# MCU.net
KiCad netlist of a schematic drawn in Altium Designer
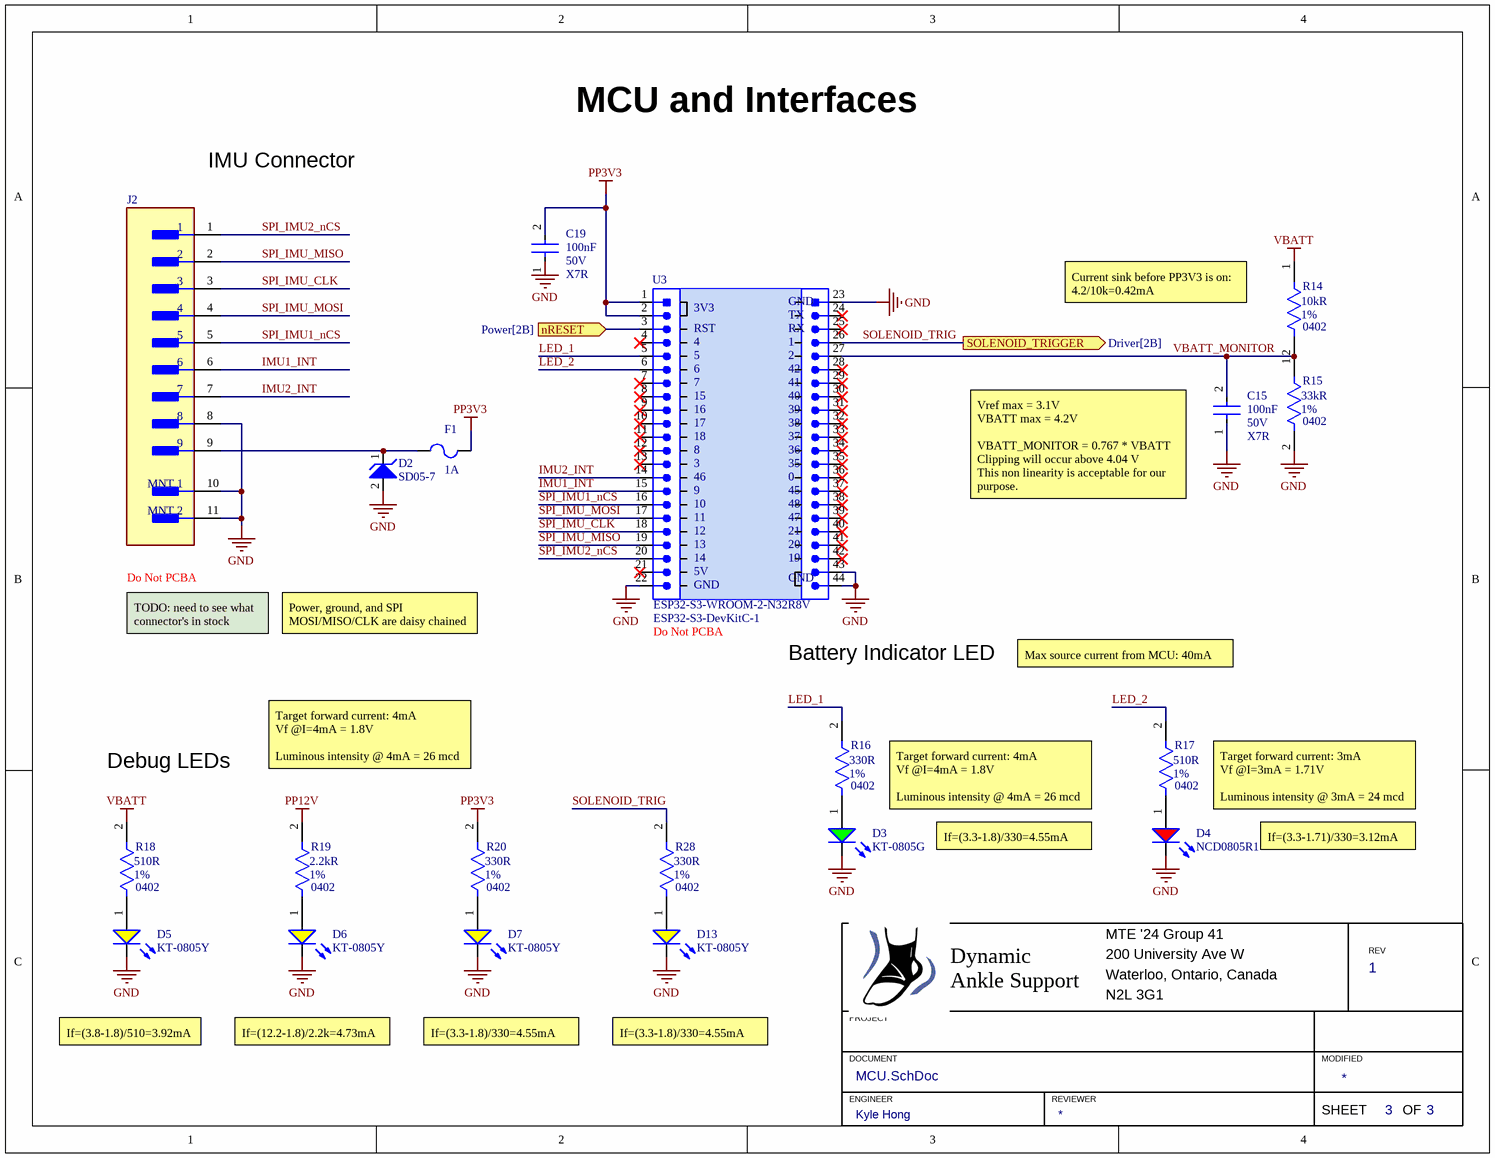
[diagram p0: MCU.SchDoc]

(export (version "E")
  (design (tool "Eeschema 10.0.6"))
  (components
    (comp (ref "C15")
      (value "CL05B104KB54PNC")
      (footprint "CAP0402")
      (description "50V 100nF X7R ±10% 0402  Multilayer Ceramic Capacitors MLCC - SMD/SMT ROHS")
      (fields
        (field (name "TOLERANCE") "±20%")
        (field (name "MANUFACTURER") "Samsung Electro-Mechanics")
        (field (name "DIELECTRIC") "X7R")
        (field (name "VOLTAGE RATING") "50V")
        (field (name "CAPACITANCE") "100nF")
      )
      (libsource (lib "FYDP_library_sch") (part "CAP0402"))
    )
    (comp (ref "C19")
      (value "CL05B104KB54PNC")
      (footprint "CAP0402")
      (description "50V 100nF X7R ±10% 0402  Multilayer Ceramic Capacitors MLCC - SMD/SMT ROHS")
      (fields
        (field (name "TOLERANCE") "±20%")
        (field (name "MANUFACTURER") "Samsung Electro-Mechanics")
        (field (name "DIELECTRIC") "X7R")
        (field (name "VOLTAGE RATING") "50V")
        (field (name "CAPACITANCE") "100nF")
      )
      (libsource (lib "FYDP_library_sch") (part "CAP0402"))
    )
    (comp (ref "D2")
      (value "SD05-7")
      (footprint "SD05-7")
      (description "TVS UNI14.5V 6.2V 5V SOD-323")
      (fields (field (name "MANUFACTURER") "Diodes Incorporated"))
      (libsource (lib "FYDP_library_sch") (part "SD05-7"))
    )
    (comp (ref "D3")
      (value "KT-0805G")
      (footprint "LED_0805_GREEN")
      (description "Emerald 0805  Light Emitting Diodes (LED) ROHS")
      (fields (field (name "MANUFACTURER") "Hubei KENTO Elec"))
      (libsource (lib "FYDP_library_sch") (part "LED_GREEN"))
    )
    (comp (ref "D4")
      (value "NCD0805R1")
      (footprint "LED_0805_RED")
      (fields (field (name "MANUFACTURER") "Foshan NationStar Optoelectronics"))
      (libsource (lib "FYDP_library_sch") (part "LED_RED"))
    )
    (comp (ref "D5")
      (value "KT-0805Y")
      (footprint "LED_0805_YELLOW")
      (description "Yellow 0805  Light Emitting Diodes (LED) ROHS")
      (fields (field (name "MANUFACTURER") "Hubei KENTO Elec"))
      (libsource (lib "FYDP_library_sch") (part "LED_YELLOW"))
    )
    (comp (ref "D6")
      (value "KT-0805Y")
      (footprint "LED_0805_YELLOW")
      (description "Yellow 0805  Light Emitting Diodes (LED) ROHS")
      (fields (field (name "MANUFACTURER") "Hubei KENTO Elec"))
      (libsource (lib "FYDP_library_sch") (part "LED_YELLOW"))
    )
    (comp (ref "D7")
      (value "KT-0805Y")
      (footprint "LED_0805_YELLOW")
      (description "Yellow 0805  Light Emitting Diodes (LED) ROHS")
      (fields (field (name "MANUFACTURER") "Hubei KENTO Elec"))
      (libsource (lib "FYDP_library_sch") (part "LED_YELLOW"))
    )
    (comp (ref "D13")
      (value "KT-0805Y")
      (footprint "LED_0805_YELLOW")
      (description "Yellow 0805  Light Emitting Diodes (LED) ROHS")
      (fields (field (name "MANUFACTURER") "Hubei KENTO Elec"))
      (libsource (lib "FYDP_library_sch") (part "LED_YELLOW"))
    )
    (comp (ref "F1")
      (value "0467001.NRHF")
      (footprint "FUSE_0603")
      (description "50A SMD Fuse 1A 32V 32V 0603  Fuses ROHS")
      (fields (field (name "MANUFACTURER") "Littelfuse") (field (name "CURRENT RATING") "1A"))
      (libsource (lib "FYDP_library_sch") (part "FUSE0603"))
    )
    (comp (ref "J2")
      (value "S9B-PH-SM4-TB(LF)(SN)")
      (footprint "FP-S9B-PH-SM4-TB_LF_SN-MFG")
      (description "CONN HEADER SMD R/A 9POS 2MM")
      (libsource (lib "Altium Content Vault") (part "1768e92021096bf704ffca471e34b85"))
    )
    (comp (ref "R14")
      (value "0402WGF1002TCE")
      (footprint "RES0402")
      (description "62.5mW Thick Film Resistors ±100ppm/℃ ±1% 10kΩ 0402  Chip Resistor - Surface Mount ROHS")
      (fields
        (field (name "MANUFACTURER") "UNI-ROYAL(Uniroyal Elec)")
        (field (name "TOLERANCE") "1%")
        (field (name "RESISTANCE") "10kR")
        (field (name "PACKAGE") "0402")
      )
      (libsource (lib "FYDP_library_sch") (part "RES0402"))
    )
    (comp (ref "R15")
      (value "0402WGF3302TCE")
      (footprint "RES0402")
      (description "62.5mW Thick Film Resistors ±100ppm/℃ ±1% 33kΩ 0402  Chip Resistor - Surface Mount ROHS")
      (fields
        (field (name "MANUFACTURER") "UNI-ROYAL(Uniroyal Elec)")
        (field (name "TOLERANCE") "1%")
        (field (name "RESISTANCE") "33kR")
        (field (name "PACKAGE") "0402")
      )
      (libsource (lib "FYDP_library_sch") (part "RES0402"))
    )
    (comp (ref "R16")
      (value "0402WGF3300TCE")
      (footprint "RES0402")
      (description "62.5mW Thick Film Resistors ±100ppm/℃ ±1% 330Ω 0402  Chip Resistor - Surface Mount ROHS")
      (fields
        (field (name "MANUFACTURER") "UNI-ROYAL(Uniroyal Elec)")
        (field (name "TOLERANCE") "1%")
        (field (name "RESISTANCE") "330R")
        (field (name "PACKAGE") "0402")
      )
      (libsource (lib "FYDP_library_sch") (part "RES0402"))
    )
    (comp (ref "R17")
      (value "0402WGF5100TCE")
      (footprint "RES0402")
      (description "62.5mW Thick Film Resistors ±100ppm/℃ ±1% 510Ω 0402  Chip Resistor - Surface Mount ROHS")
      (fields
        (field (name "MANUFACTURER") "UNI-ROYAL(Uniroyal Elec)")
        (field (name "TOLERANCE") "1%")
        (field (name "RESISTANCE") "510R")
        (field (name "PACKAGE") "0402")
      )
      (libsource (lib "FYDP_library_sch") (part "RES0402"))
    )
    (comp (ref "R18")
      (value "0402WGF5100TCE")
      (footprint "RES0402")
      (description "62.5mW Thick Film Resistors ±100ppm/℃ ±1% 510Ω 0402  Chip Resistor - Surface Mount ROHS")
      (fields
        (field (name "MANUFACTURER") "UNI-ROYAL(Uniroyal Elec)")
        (field (name "TOLERANCE") "1%")
        (field (name "RESISTANCE") "510R")
        (field (name "PACKAGE") "0402")
      )
      (libsource (lib "FYDP_library_sch") (part "RES0402"))
    )
    (comp (ref "R19")
      (value "0402WGF2201TCE")
      (footprint "RES0402")
      (description "62.5mW Thick Film Resistors ±100ppm/℃ ±1% 2.2kΩ 0402  Chip Resistor - Surface Mount ROHS")
      (fields
        (field (name "MANUFACTURER") "UNI-ROYAL(Uniroyal Elec)")
        (field (name "TOLERANCE") "1%")
        (field (name "RESISTANCE") "2.2kR")
        (field (name "PACKAGE") "0402")
      )
      (libsource (lib "FYDP_library_sch") (part "RES0402"))
    )
    (comp (ref "R20")
      (value "0402WGF3300TCE")
      (footprint "RES0402")
      (description "62.5mW Thick Film Resistors ±100ppm/℃ ±1% 330Ω 0402  Chip Resistor - Surface Mount ROHS")
      (fields
        (field (name "MANUFACTURER") "UNI-ROYAL(Uniroyal Elec)")
        (field (name "TOLERANCE") "1%")
        (field (name "RESISTANCE") "330R")
        (field (name "PACKAGE") "0402")
      )
      (libsource (lib "FYDP_library_sch") (part "RES0402"))
    )
    (comp (ref "R28")
      (value "0402WGF3300TCE")
      (footprint "RES0402")
      (description "62.5mW Thick Film Resistors ±100ppm/℃ ±1% 330Ω 0402  Chip Resistor - Surface Mount ROHS")
      (fields
        (field (name "MANUFACTURER") "UNI-ROYAL(Uniroyal Elec)")
        (field (name "TOLERANCE") "1%")
        (field (name "RESISTANCE") "330R")
        (field (name "PACKAGE") "0402")
      )
      (libsource (lib "FYDP_library_sch") (part "RES0402"))
    )
    (comp (ref "U3")
      (value "ESP32-S3-WROOM-2-N32R8V")
      (footprint "EPS32-S3-DevKitC")
      (fields
        (field (name "MCU PART NUMBER") "ESP32-S3-WROOM-2-N32R8V")
        (field (name "DEV KIT PART NUMBER") "ESP32-S3-DevKitC-1")
      )
      (libsource (lib "FYDP_library_sch") (part "EPS32-S3-DevKitC"))
    )
  )
  (nets
    (net (code "1") (name "/IMU1_INT") (class "Default")
      (node (ref "J2") (pin "6") (pinfunction "6_6") (pintype "passive"))
      (node (ref "U3") (pin "15") (pinfunction "15_15") (pintype "passive"))
    )
    (net (code "2") (name "/IMU2_INT") (class "Default")
      (node (ref "J2") (pin "7") (pinfunction "7_7") (pintype "passive"))
      (node (ref "U3") (pin "14") (pinfunction "14_14") (pintype "passive"))
    )
    (net (code "3") (name "/LED_1") (class "Default")
      (node (ref "R16") (pin "2") (pinfunction "2_2") (pintype "passive"))
      (node (ref "U3") (pin "5") (pinfunction "5_5") (pintype "passive"))
    )
    (net (code "4") (name "/LED_2") (class "Default")
      (node (ref "R17") (pin "2") (pinfunction "2_2") (pintype "passive"))
      (node (ref "U3") (pin "6") (pinfunction "6_6") (pintype "passive"))
    )
    (net (code "5") (name "/SOLENOID_TRIG") (class "Default")
      (node (ref "R28") (pin "2") (pinfunction "2_2") (pintype "passive"))
      (node (ref "U3") (pin "26") (pinfunction "26_26") (pintype "passive"))
    )
    (net (code "6") (name "/SPI_IMU1_nCS") (class "Default")
      (node (ref "J2") (pin "5") (pinfunction "5_5") (pintype "passive"))
      (node (ref "U3") (pin "16") (pinfunction "16_16") (pintype "passive"))
    )
    (net (code "7") (name "/SPI_IMU2_nCS") (class "Default")
      (node (ref "J2") (pin "1") (pinfunction "1_1") (pintype "passive"))
      (node (ref "U3") (pin "20") (pinfunction "20_20") (pintype "passive"))
    )
    (net (code "8") (name "/SPI_IMU_CLK") (class "Default")
      (node (ref "J2") (pin "3") (pinfunction "3_3") (pintype "passive"))
      (node (ref "U3") (pin "18") (pinfunction "18_18") (pintype "passive"))
    )
    (net (code "9") (name "/SPI_IMU_MISO") (class "Default")
      (node (ref "J2") (pin "2") (pinfunction "2_2") (pintype "passive"))
      (node (ref "U3") (pin "19") (pinfunction "19_19") (pintype "passive"))
    )
    (net (code "10") (name "/SPI_IMU_MOSI") (class "Default")
      (node (ref "J2") (pin "4") (pinfunction "4_4") (pintype "passive"))
      (node (ref "U3") (pin "17") (pinfunction "17_17") (pintype "passive"))
    )
    (net (code "11") (name "/VBATT_MONITOR") (class "Default")
      (node (ref "C15") (pin "2") (pinfunction "2_2") (pintype "passive"))
      (node (ref "R14") (pin "2") (pinfunction "2_2") (pintype "passive"))
      (node (ref "R15") (pin "1") (pinfunction "1_1") (pintype "passive"))
      (node (ref "U3") (pin "27") (pinfunction "27_27") (pintype "passive"))
    )
    (net (code "12") (name "/nRESET") (class "Default")
      (node (ref "U3") (pin "3") (pinfunction "3_3") (pintype "passive"))
    )
    (net (code "13") (name "GND") (class "Default")
      (node (ref "C15") (pin "1") (pinfunction "1_1") (pintype "passive"))
      (node (ref "C19") (pin "1") (pinfunction "1_1") (pintype "passive"))
      (node (ref "D13") (pin "1") (pinfunction "K_1") (pintype "passive"))
      (node (ref "D2") (pin "2") (pinfunction "2_2") (pintype "passive"))
      (node (ref "D3") (pin "1") (pinfunction "K_1") (pintype "passive"))
      (node (ref "D4") (pin "1") (pinfunction "K_1") (pintype "passive"))
      (node (ref "D5") (pin "1") (pinfunction "K_1") (pintype "passive"))
      (node (ref "D6") (pin "1") (pinfunction "K_1") (pintype "passive"))
      (node (ref "D7") (pin "1") (pinfunction "K_1") (pintype "passive"))
      (node (ref "J2") (pin "10") (pinfunction "MNT_1_10") (pintype "passive"))
      (node (ref "J2") (pin "11") (pinfunction "MNT_2_11") (pintype "passive"))
      (node (ref "J2") (pin "8") (pinfunction "8_8") (pintype "passive"))
      (node (ref "R15") (pin "2") (pinfunction "2_2") (pintype "passive"))
      (node (ref "U3") (pin "22") (pinfunction "22_22") (pintype "passive"))
      (node (ref "U3") (pin "23") (pinfunction "23_23") (pintype "passive"))
      (node (ref "U3") (pin "43") (pinfunction "43_43") (pintype "passive"))
      (node (ref "U3") (pin "44") (pinfunction "44_44") (pintype "passive"))
    )
    (net (code "14") (name "Net-(D2-Pad1)") (class "Default")
      (node (ref "D2") (pin "1") (pinfunction "1_1") (pintype "passive"))
      (node (ref "F1") (pin "1") (pinfunction "1_1") (pintype "passive"))
      (node (ref "J2") (pin "9") (pinfunction "9_9") (pintype "passive"))
    )
    (net (code "15") (name "Net-(D3-A)") (class "Default")
      (node (ref "D3") (pin "2") (pinfunction "A_2") (pintype "passive"))
      (node (ref "R16") (pin "1") (pinfunction "1_1") (pintype "passive"))
    )
    (net (code "16") (name "Net-(D4-A)") (class "Default")
      (node (ref "D4") (pin "2") (pinfunction "A_2") (pintype "passive"))
      (node (ref "R17") (pin "1") (pinfunction "1_1") (pintype "passive"))
    )
    (net (code "17") (name "Net-(D5-A)") (class "Default")
      (node (ref "D5") (pin "2") (pinfunction "A_2") (pintype "passive"))
      (node (ref "R18") (pin "1") (pinfunction "1_1") (pintype "passive"))
    )
    (net (code "18") (name "Net-(D6-A)") (class "Default")
      (node (ref "D6") (pin "2") (pinfunction "A_2") (pintype "passive"))
      (node (ref "R19") (pin "1") (pinfunction "1_1") (pintype "passive"))
    )
    (net (code "19") (name "Net-(D7-A)") (class "Default")
      (node (ref "D7") (pin "2") (pinfunction "A_2") (pintype "passive"))
      (node (ref "R20") (pin "1") (pinfunction "1_1") (pintype "passive"))
    )
    (net (code "20") (name "Net-(D13-A)") (class "Default")
      (node (ref "D13") (pin "2") (pinfunction "A_2") (pintype "passive"))
      (node (ref "R28") (pin "1") (pinfunction "1_1") (pintype "passive"))
    )
    (net (code "21") (name "PP3V3") (class "Default")
      (node (ref "C19") (pin "2") (pinfunction "2_2") (pintype "passive"))
      (node (ref "F1") (pin "2") (pinfunction "2_2") (pintype "passive"))
      (node (ref "R20") (pin "2") (pinfunction "2_2") (pintype "passive"))
      (node (ref "U3") (pin "1") (pinfunction "1_1") (pintype "passive"))
      (node (ref "U3") (pin "2") (pinfunction "2_2") (pintype "passive"))
    )
    (net (code "22") (name "PP12V") (class "Default")
      (node (ref "R19") (pin "2") (pinfunction "2_2") (pintype "passive"))
    )
    (net (code "23") (name "VBATT") (class "Default")
      (node (ref "R14") (pin "1") (pinfunction "1_1") (pintype "passive"))
      (node (ref "R18") (pin "2") (pinfunction "2_2") (pintype "passive"))
    )
    (net (code "24") (name "unconnected-(U3-6-Pad7)") (class "Default")
      (node (ref "U3") (pin "7") (pinfunction "6_7") (pintype "passive+no_connect"))
    )
    (net (code "25") (name "unconnected-(U3-6-Pad8)") (class "Default")
      (node (ref "U3") (pin "8") (pinfunction "6_8") (pintype "passive+no_connect"))
    )
    (net (code "26") (name "unconnected-(U3-Pad4)") (class "Default")
      (node (ref "U3") (pin "4") (pinfunction "4_4") (pintype "passive+no_connect"))
    )
    (net (code "27") (name "unconnected-(U3-Pad9)") (class "Default")
      (node (ref "U3") (pin "9") (pinfunction "9_9") (pintype "passive+no_connect"))
    )
    (net (code "28") (name "unconnected-(U3-Pad10)") (class "Default")
      (node (ref "U3") (pin "10") (pinfunction "10_10") (pintype "passive+no_connect"))
    )
    (net (code "29") (name "unconnected-(U3-Pad11)") (class "Default")
      (node (ref "U3") (pin "11") (pinfunction "11_11") (pintype "passive+no_connect"))
    )
    (net (code "30") (name "unconnected-(U3-Pad12)") (class "Default")
      (node (ref "U3") (pin "12") (pinfunction "12_12") (pintype "passive+no_connect"))
    )
    (net (code "31") (name "unconnected-(U3-Pad13)") (class "Default")
      (node (ref "U3") (pin "13") (pinfunction "13_13") (pintype "passive+no_connect"))
    )
    (net (code "32") (name "unconnected-(U3-Pad21)") (class "Default")
      (node (ref "U3") (pin "21") (pinfunction "21_21") (pintype "passive+no_connect"))
    )
    (net (code "33") (name "unconnected-(U3-Pad24)") (class "Default")
      (node (ref "U3") (pin "24") (pinfunction "24_24") (pintype "passive+no_connect"))
    )
    (net (code "34") (name "unconnected-(U3-Pad25)") (class "Default")
      (node (ref "U3") (pin "25") (pinfunction "25_25") (pintype "passive+no_connect"))
    )
    (net (code "35") (name "unconnected-(U3-Pad28)") (class "Default")
      (node (ref "U3") (pin "28") (pinfunction "28_28") (pintype "passive+no_connect"))
    )
    (net (code "36") (name "unconnected-(U3-Pad29)") (class "Default")
      (node (ref "U3") (pin "29") (pinfunction "29_29") (pintype "passive+no_connect"))
    )
    (net (code "37") (name "unconnected-(U3-Pad30)") (class "Default")
      (node (ref "U3") (pin "30") (pinfunction "30_30") (pintype "passive+no_connect"))
    )
    (net (code "38") (name "unconnected-(U3-Pad31)") (class "Default")
      (node (ref "U3") (pin "31") (pinfunction "31_31") (pintype "passive+no_connect"))
    )
    (net (code "39") (name "unconnected-(U3-Pad32)") (class "Default")
      (node (ref "U3") (pin "32") (pinfunction "32_32") (pintype "passive+no_connect"))
    )
    (net (code "40") (name "unconnected-(U3-Pad33)") (class "Default")
      (node (ref "U3") (pin "33") (pinfunction "33_33") (pintype "passive+no_connect"))
    )
    (net (code "41") (name "unconnected-(U3-Pad34)") (class "Default")
      (node (ref "U3") (pin "34") (pinfunction "34_34") (pintype "passive+no_connect"))
    )
    (net (code "42") (name "unconnected-(U3-Pad35)") (class "Default")
      (node (ref "U3") (pin "35") (pinfunction "35_35") (pintype "passive+no_connect"))
    )
    (net (code "43") (name "unconnected-(U3-Pad36)") (class "Default")
      (node (ref "U3") (pin "36") (pinfunction "36_36") (pintype "passive+no_connect"))
    )
    (net (code "44") (name "unconnected-(U3-Pad37)") (class "Default")
      (node (ref "U3") (pin "37") (pinfunction "37_37") (pintype "passive+no_connect"))
    )
    (net (code "45") (name "unconnected-(U3-Pad38)") (class "Default")
      (node (ref "U3") (pin "38") (pinfunction "38_38") (pintype "passive+no_connect"))
    )
    (net (code "46") (name "unconnected-(U3-Pad39)") (class "Default")
      (node (ref "U3") (pin "39") (pinfunction "39_39") (pintype "passive+no_connect"))
    )
    (net (code "47") (name "unconnected-(U3-Pad40)") (class "Default")
      (node (ref "U3") (pin "40") (pinfunction "40_40") (pintype "passive+no_connect"))
    )
    (net (code "48") (name "unconnected-(U3-Pad41)") (class "Default")
      (node (ref "U3") (pin "41") (pinfunction "41_41") (pintype "passive+no_connect"))
    )
    (net (code "49") (name "unconnected-(U3-Pad42)") (class "Default")
      (node (ref "U3") (pin "42") (pinfunction "42_42") (pintype "passive+no_connect"))
    )
  )
)
